# Granny_Safe_all_Inclusive.net
KiCad netlist of a schematic drawn in EAGLE
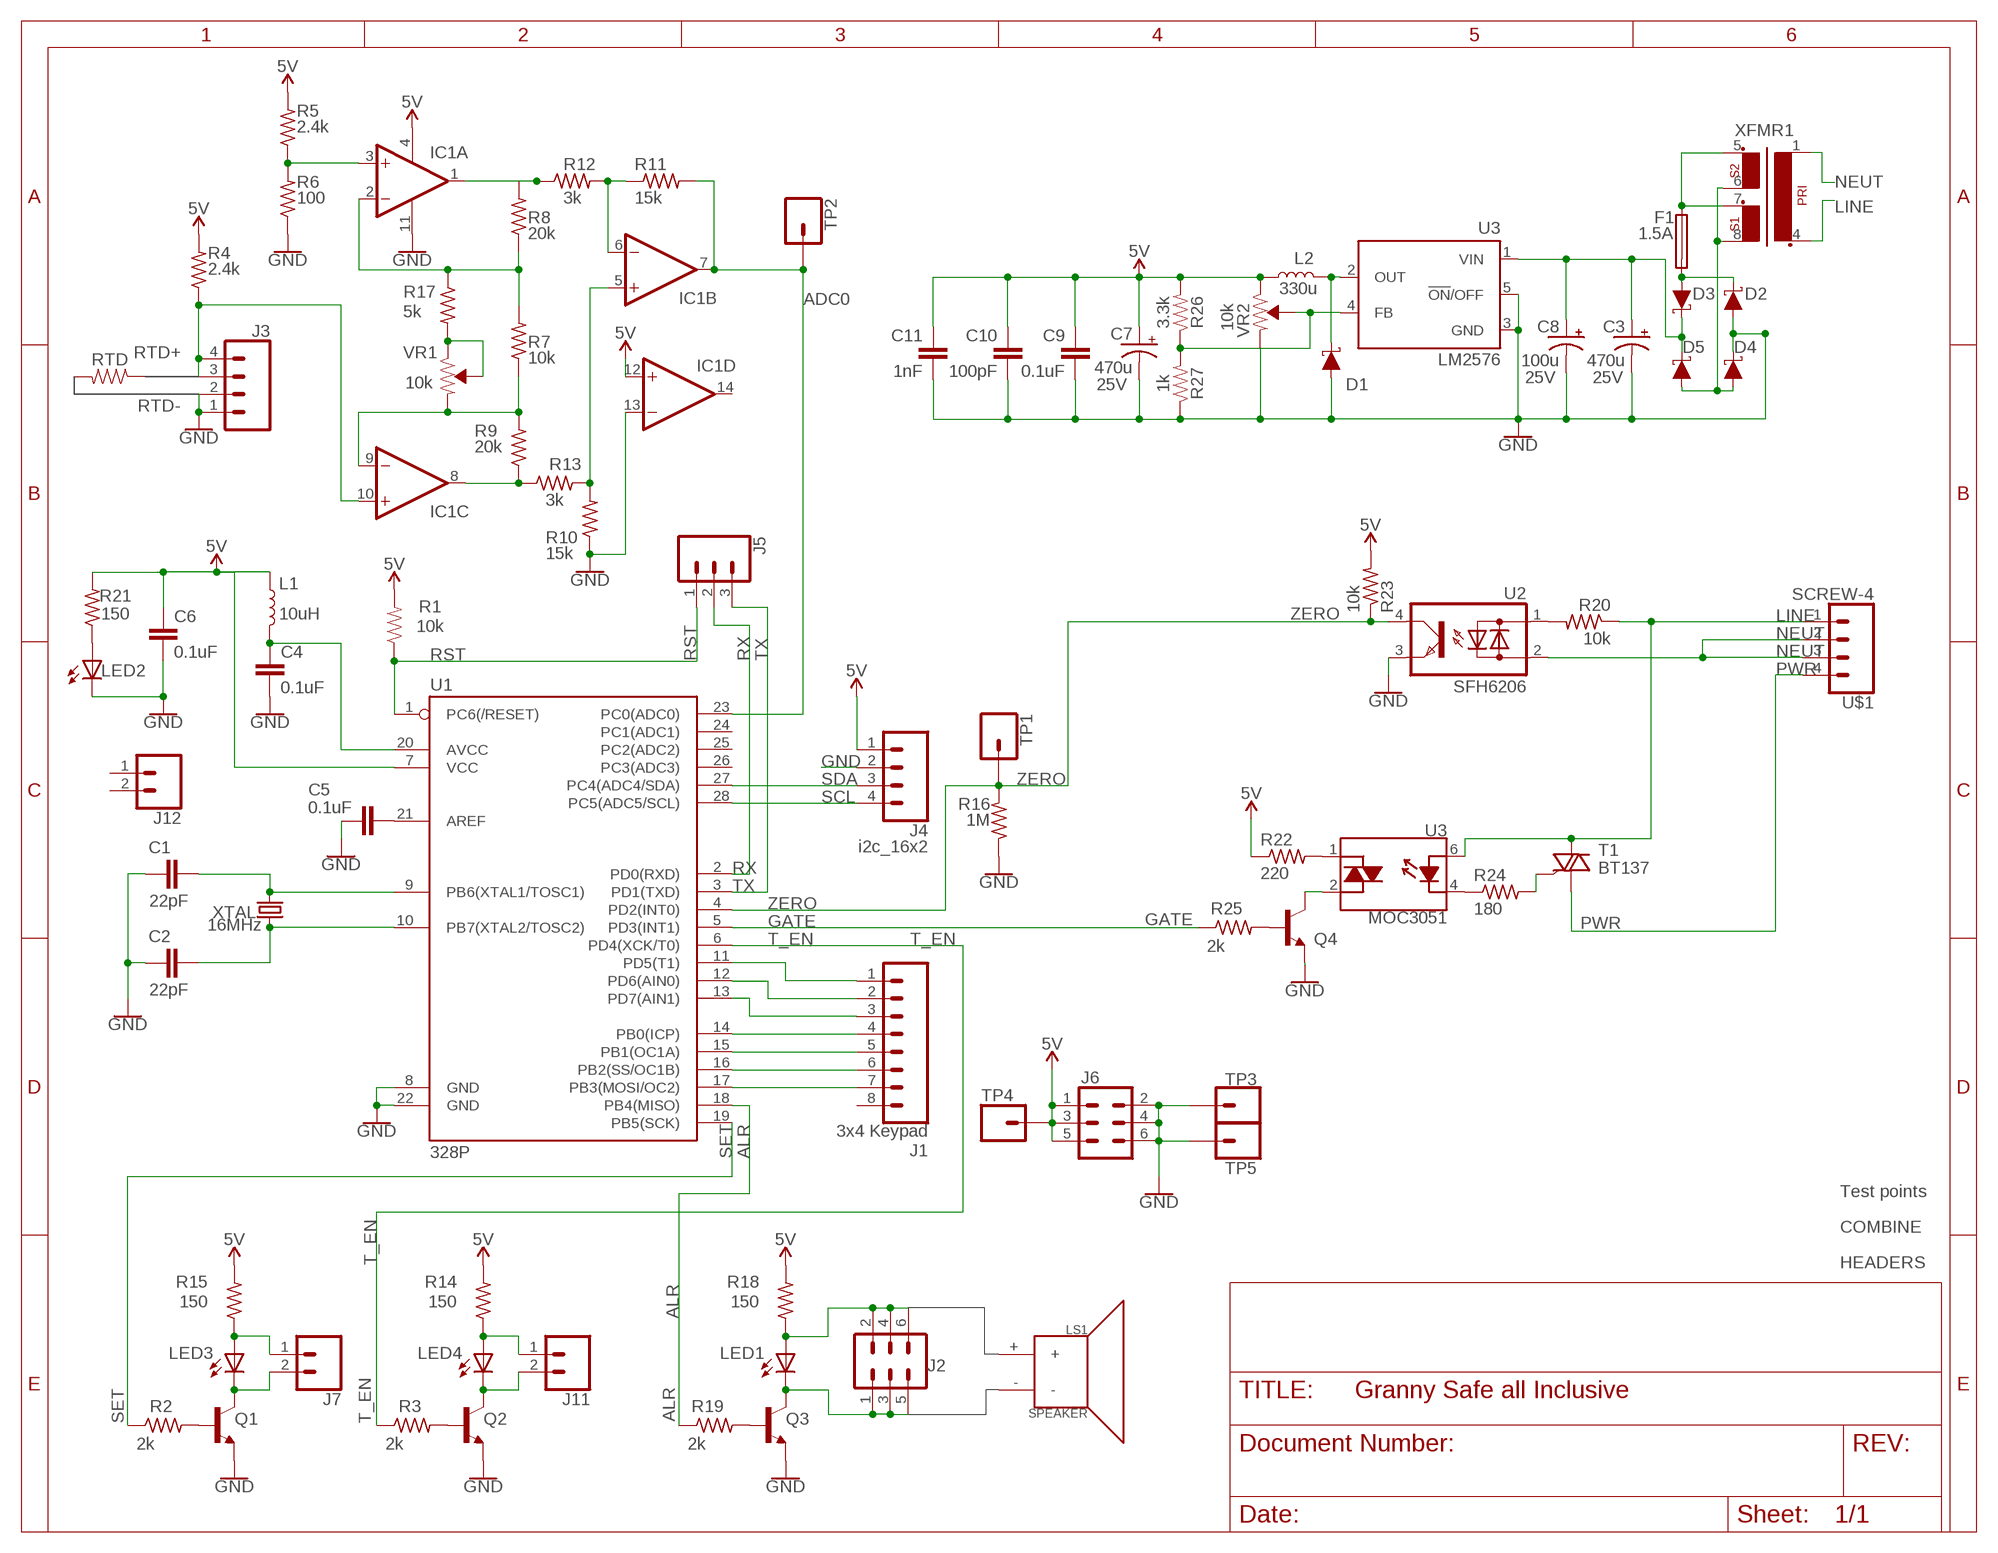
[diagram p0: schematic, sheet 1]

(export (version "E")
  (design (tool "Eeschema 10.0.6"))
  (components
    (comp (ref "C1")
      (value "22pF")
      (footprint "eagle-import:0603")
      (libsource (lib "eagle-import") (part "22PF-0603-50V-5%"))
    )
    (comp (ref "C2")
      (value "22pF")
      (footprint "eagle-import:0603")
      (libsource (lib "eagle-import") (part "22PF-0603-50V-5%"))
    )
    (comp (ref "C3")
      (value "470u")
      (footprint "eagle-import:E3,5-8")
      (libsource (lib "eagle-import") (part "CPOL-USE3.5-8"))
    )
    (comp (ref "C4")
      (value "0.1uF")
      (footprint "eagle-import:0603")
      (libsource (lib "eagle-import") (part "0.1UF-0603-25V-(+80/-20%)"))
    )
    (comp (ref "C5")
      (value "0.1uF")
      (footprint "eagle-import:0603")
      (libsource (lib "eagle-import") (part "0.1UF-0603-25V-(+80/-20%)"))
    )
    (comp (ref "C6")
      (value "0.1uF")
      (footprint "eagle-import:0603")
      (libsource (lib "eagle-import") (part "0.1UF-0603-25V-(+80/-20%)"))
    )
    (comp (ref "C7")
      (value "470u")
      (footprint "eagle-import:E3,5-8")
      (libsource (lib "eagle-import") (part "CPOL-USE3.5-8"))
    )
    (comp (ref "C8")
      (value "100u")
      (footprint "eagle-import:E2-5")
      (libsource (lib "eagle-import") (part "CPOL-USE2-5"))
    )
    (comp (ref "C9")
      (value "0.1uF")
      (footprint "eagle-import:0603")
      (libsource (lib "eagle-import") (part "0.1UF-0603-25V-5%"))
    )
    (comp (ref "C10")
      (value "100pF")
      (footprint "eagle-import:0603")
      (libsource (lib "eagle-import") (part "100PF-0603-50V-5%"))
    )
    (comp (ref "C11")
      (value "1nF")
      (footprint "eagle-import:0603")
      (libsource (lib "eagle-import") (part "1.0NF/1000PF-0603-50V-10%"))
    )
    (comp (ref "D1")
      (value "DIODE-SCHOTTKY-B340A")
      (footprint "eagle-import:SMA-DIODE")
      (libsource (lib "eagle-import") (part "DIODE-SCHOTTKY-B340A"))
    )
    (comp (ref "D2")
      (value "DIODE-SCHOTTKY-B340A")
      (footprint "eagle-import:SMA-DIODE")
      (libsource (lib "eagle-import") (part "DIODE-SCHOTTKY-B340A"))
    )
    (comp (ref "D3")
      (value "DIODE-SCHOTTKY-B340A")
      (footprint "eagle-import:SMA-DIODE")
      (libsource (lib "eagle-import") (part "DIODE-SCHOTTKY-B340A"))
    )
    (comp (ref "D4")
      (value "DIODE-SCHOTTKY-B340A")
      (footprint "eagle-import:SMA-DIODE")
      (libsource (lib "eagle-import") (part "DIODE-SCHOTTKY-B340A"))
    )
    (comp (ref "D5")
      (value "DIODE-SCHOTTKY-B340A")
      (footprint "eagle-import:SMA-DIODE")
      (libsource (lib "eagle-import") (part "DIODE-SCHOTTKY-B340A"))
    )
    (comp (ref "F1")
      (value "1.5A")
      (footprint "eagle-import:TE5")
      (libsource (lib "eagle-import") (part "TE5"))
    )
    (comp (ref "IC1")
      (value "MCP604SL")
      (footprint "eagle-import:SO14")
      (libsource (lib "eagle-import") (part "MCP604SL"))
    )
    (comp (ref "IC2")
      (value "LM2596S")
      (footprint "eagle-import:TO263-5")
      (fields (field (name "MF") "NATIONAL SEMICONDUCTOR") (field (name "MPN") "LM2596S-ADJ/NOPB"))
      (libsource (lib "eagle-import") (part "LM2596S"))
    )
    (comp (ref "J1")
      (value "3x4 Keypad")
      (footprint "eagle-import:1X08")
      (libsource (lib "eagle-import") (part "CONN_08{dblquote}"))
    )
    (comp (ref "J2")
      (value "FEMALE 2x3")
      (footprint "eagle-import:2X3")
      (libsource (lib "eagle-import") (part "CONN_03X2FEMALE"))
    )
    (comp (ref "J3")
      (value "SCREW-4")
      (footprint "eagle-import:SCREWTERMINAL-5MM-2")
      (libsource (lib "eagle-import") (part "SCREW-4"))
    )
    (comp (ref "J4")
      (value "i2c_16x2")
      (footprint "eagle-import:1X04")
      (libsource (lib "eagle-import") (part "CONN_04"))
    )
    (comp (ref "J5")
      (value "CONN_03")
      (footprint "eagle-import:1X03")
      (libsource (lib "eagle-import") (part "CONN_03"))
    )
    (comp (ref "J6")
      (value "FEMALE 2x3")
      (footprint "eagle-import:2X3")
      (libsource (lib "eagle-import") (part "CONN_03X2FEMALE"))
    )
    (comp (ref "J7")
      (value "CONN_02")
      (footprint "eagle-import:1X02")
      (libsource (lib "eagle-import") (part "CONN_02"))
    )
    (comp (ref "J11")
      (value "CONN_02")
      (footprint "eagle-import:1X02")
      (libsource (lib "eagle-import") (part "CONN_02"))
    )
    (comp (ref "J12")
      (value "CONN_02")
      (footprint "eagle-import:1X02")
      (libsource (lib "eagle-import") (part "CONN_02"))
    )
    (comp (ref "L1")
      (value "10uH")
      (footprint "eagle-import:0603")
      (libsource (lib "eagle-import") (part "INDUCTOR-0603-33NH"))
    )
    (comp (ref "L2")
      (value "INDUCTOR")
      (footprint "eagle-import:CR75")
      (libsource (lib "eagle-import") (part "INDUCTOR"))
    )
    (comp (ref "LED1")
      (value "LED5MM")
      (footprint "eagle-import:LED5MM")
      (libsource (lib "eagle-import") (part "LED5MM"))
    )
    (comp (ref "LED2")
      (value "LED5MM")
      (footprint "eagle-import:LED5MM")
      (libsource (lib "eagle-import") (part "LED5MM"))
    )
    (comp (ref "LED3")
      (value "LED5MM")
      (footprint "eagle-import:LED5MM")
      (libsource (lib "eagle-import") (part "LED5MM"))
    )
    (comp (ref "LED4")
      (value "LED5MM")
      (footprint "eagle-import:LED5MM")
      (libsource (lib "eagle-import") (part "LED5MM"))
    )
    (comp (ref "LS1")
      (value "SPEAKER")
      (footprint "eagle-import:PCB_MOUNT_SPEAKER")
      (libsource (lib "eagle-import") (part "SPEAKER"))
    )
    (comp (ref "Q1")
      (value "TRANS_NPN-MMBTA42")
      (footprint "eagle-import:SOT23-3")
      (libsource (lib "eagle-import") (part "TRANS_NPN-MMBTA42"))
    )
    (comp (ref "Q2")
      (value "TRANS_NPN-MMBTA42")
      (footprint "eagle-import:SOT23-3")
      (libsource (lib "eagle-import") (part "TRANS_NPN-MMBTA42"))
    )
    (comp (ref "Q3")
      (value "TRANS_NPN-MMBTA42")
      (footprint "eagle-import:SOT23-3")
      (libsource (lib "eagle-import") (part "TRANS_NPN-MMBTA42"))
    )
    (comp (ref "Q4")
      (value "2N3904")
      (footprint "eagle-import:SOT23-3")
      (libsource (lib "eagle-import") (part "TRANS_NPN-MMBTA42"))
    )
    (comp (ref "R1")
      (value "10k")
      (footprint "eagle-import:0603")
      (libsource (lib "eagle-import") (part "10KOHM-0603-1/10W-1%"))
    )
    (comp (ref "R2")
      (value "2k")
      (footprint "eagle-import:R0603")
      (libsource (lib "eagle-import") (part "R-US_R0603"))
    )
    (comp (ref "R3")
      (value "2k")
      (footprint "eagle-import:R0603")
      (libsource (lib "eagle-import") (part "R-US_R0603"))
    )
    (comp (ref "R4")
      (value "2.4k")
      (footprint "eagle-import:R0603")
      (libsource (lib "eagle-import") (part "resistor_348_R-US_R0603"))
    )
    (comp (ref "R5")
      (value "2.4k")
      (footprint "eagle-import:R0603")
      (libsource (lib "eagle-import") (part "resistor_348_R-US_R0603"))
    )
    (comp (ref "R6")
      (value "100")
      (footprint "eagle-import:R0603")
      (libsource (lib "eagle-import") (part "resistor_348_R-US_R0603"))
    )
    (comp (ref "R7")
      (value "10k")
      (footprint "eagle-import:R0603")
      (libsource (lib "eagle-import") (part "resistor_348_R-US_R0603"))
    )
    (comp (ref "R8")
      (value "20k")
      (footprint "eagle-import:R0603")
      (libsource (lib "eagle-import") (part "resistor_348_R-US_R0603"))
    )
    (comp (ref "R9")
      (value "20k")
      (footprint "eagle-import:R0603")
      (libsource (lib "eagle-import") (part "resistor_348_R-US_R0603"))
    )
    (comp (ref "R10")
      (value "15k")
      (footprint "eagle-import:R0603")
      (libsource (lib "eagle-import") (part "resistor_348_R-US_R0603"))
    )
    (comp (ref "R11")
      (value "15k")
      (footprint "eagle-import:R0603")
      (libsource (lib "eagle-import") (part "resistor_348_R-US_R0603"))
    )
    (comp (ref "R12")
      (value "3k")
      (footprint "eagle-import:R0603")
      (libsource (lib "eagle-import") (part "resistor_348_R-US_R0603"))
    )
    (comp (ref "R13")
      (value "3k")
      (footprint "eagle-import:R0603")
      (libsource (lib "eagle-import") (part "resistor_348_R-US_R0603"))
    )
    (comp (ref "R14")
      (value "150")
      (footprint "eagle-import:R0603")
      (libsource (lib "eagle-import") (part "R-US_R0603"))
    )
    (comp (ref "R15")
      (value "150")
      (footprint "eagle-import:R0603")
      (libsource (lib "eagle-import") (part "R-US_R0603"))
    )
    (comp (ref "R16")
      (value "1M")
      (footprint "eagle-import:R0603")
      (libsource (lib "eagle-import") (part "resistor_348_R-US_R0603"))
    )
    (comp (ref "R17")
      (value "5k")
      (footprint "eagle-import:R0603")
      (libsource (lib "eagle-import") (part "resistor_348_R-US_R0603"))
    )
    (comp (ref "R18")
      (value "150")
      (footprint "eagle-import:R0603")
      (libsource (lib "eagle-import") (part "R-US_R0603"))
    )
    (comp (ref "R19")
      (value "2k")
      (footprint "eagle-import:R0603")
      (libsource (lib "eagle-import") (part "R-US_R0603"))
    )
    (comp (ref "R20")
      (value "10k")
      (footprint "eagle-import:R0603")
      (libsource (lib "eagle-import") (part "R-US_R0603"))
    )
    (comp (ref "R21")
      (value "150")
      (footprint "eagle-import:R0603")
      (libsource (lib "eagle-import") (part "R-US_R0603"))
    )
    (comp (ref "R22")
      (value "220")
      (footprint "eagle-import:R0603")
      (libsource (lib "eagle-import") (part "R-US_R0603"))
    )
    (comp (ref "R23")
      (value "10k")
      (footprint "eagle-import:R0603")
      (libsource (lib "eagle-import") (part "R-US_R0603"))
    )
    (comp (ref "R24")
      (value "180")
      (footprint "eagle-import:R0603")
      (libsource (lib "eagle-import") (part "R-US_R0603"))
    )
    (comp (ref "R25")
      (value "2k")
      (footprint "eagle-import:R0603")
      (libsource (lib "eagle-import") (part "R-US_R0603"))
    )
    (comp (ref "R26")
      (value "3.3k")
      (footprint "eagle-import:0603")
      (libsource (lib "eagle-import") (part "3.3KOHM-0603-1/10W-1%"))
    )
    (comp (ref "R27")
      (value "1k")
      (footprint "eagle-import:0603")
      (libsource (lib "eagle-import") (part "1KOHM-0603-1/10W-1%"))
    )
    (comp (ref "RTD")
      (value "10KOHM-HORIZ-1/4W-1%")
      (footprint "eagle-import:AXIAL-0.3")
      (libsource (lib "eagle-import") (part "10KOHM-HORIZ-1/4W-1%"))
    )
    (comp (ref "T1")
      (value "BT137")
      (footprint "eagle-import:TO220BV")
      (libsource (lib "eagle-import") (part "BT137"))
    )
    (comp (ref "TP1")
      (value "CONN_01")
      (footprint "eagle-import:1X01")
      (libsource (lib "eagle-import") (part "CONN_01"))
    )
    (comp (ref "TP2")
      (value "CONN_01")
      (footprint "eagle-import:1X01")
      (libsource (lib "eagle-import") (part "CONN_01"))
    )
    (comp (ref "TP3")
      (value "CONN_01")
      (footprint "eagle-import:1X01")
      (libsource (lib "eagle-import") (part "CONN_01"))
    )
    (comp (ref "TP4")
      (value "CONN_01")
      (footprint "eagle-import:1X01")
      (libsource (lib "eagle-import") (part "CONN_01"))
    )
    (comp (ref "TP5")
      (value "CONN_01")
      (footprint "eagle-import:1X01")
      (libsource (lib "eagle-import") (part "CONN_01"))
    )
    (comp (ref "U$1")
      (value "SCREW-4")
      (footprint "eagle-import:SCREWTERMINAL-5MM-2")
      (libsource (lib "eagle-import") (part "SCREW-4"))
    )
    (comp (ref "U1")
      (value "328P")
      (footprint "eagle-import:DIP28")
      (libsource (lib "eagle-import") (part "ATMEGA328P_PDIP"))
    )
    (comp (ref "U2")
      (value "SFH6206")
      (footprint "eagle-import:DIL4-SMD")
      (fields (field (name "MF") "VISHAY/TELEFUNKEN") (field (name "MPN") "SFH6206-3"))
      (libsource (lib "eagle-import") (part "SFH6206"))
    )
    (comp (ref "U3")
      (value "MOC3051")
      (footprint "eagle-import:DIP8SMD")
      (libsource (lib "eagle-import") (part "MOC3051"))
    )
    (comp (ref "VR1")
      (value "10k")
      (footprint "eagle-import:TRIMPOT-SMD-3MM-CLOSED")
      (libsource (lib "eagle-import") (part "TRIMPOT-SMD-3MM-CLOSED-1/8W-20%"))
    )
    (comp (ref "VR2")
      (value "10k")
      (footprint "eagle-import:TRIMPOT-SMD-TC33X")
      (libsource (lib "eagle-import") (part "TRIMPOT-SMD-3MM-OPEN-1/10W-25%"))
    )
    (comp (ref "XFMR1")
      (value "EE20-2")
      (footprint "eagle-import:EE20-2")
      (libsource (lib "eagle-import") (part "EE20-2"))
    )
    (comp (ref "XTAL")
      (value "16MHz")
      (footprint "eagle-import:HC49US")
      (libsource (lib "eagle-import") (part "CRYSTAL-16MHZPTH-HC49US"))
    )
  )
  (nets
    (net (code "1") (name "/ADC0") (class "Default")
      (node (ref "IC1") (pin "7") (pinfunction "OUT_7") (pintype "output"))
      (node (ref "R11") (pin "2") (pinfunction "2_2") (pintype "passive"))
      (node (ref "TP2") (pin "1") (pinfunction "1_1") (pintype "passive"))
      (node (ref "U1") (pin "23") (pinfunction "PC0(ADC0)_23") (pintype "bidirectional"))
    )
    (net (code "2") (name "/ALR") (class "Default")
      (node (ref "R19") (pin "1") (pinfunction "1_1") (pintype "passive"))
      (node (ref "U1") (pin "18") (pinfunction "PB4(MISO)_18") (pintype "bidirectional"))
    )
    (net (code "3") (name "/GATE") (class "Default")
      (node (ref "R25") (pin "1") (pinfunction "1_1") (pintype "passive"))
      (node (ref "U1") (pin "5") (pinfunction "PD3(INT1)_5") (pintype "bidirectional"))
    )
    (net (code "4") (name "/LINE") (class "Default")
      (node (ref "R20") (pin "1") (pinfunction "1_1") (pintype "passive"))
      (node (ref "T1") (pin "T2") (pinfunction "A2_T2") (pintype "passive"))
      (node (ref "U$1") (pin "1") (pinfunction "1_1") (pintype "passive"))
      (node (ref "U3") (pin "6") (pinfunction "6_6") (pintype "bidirectional"))
      (node (ref "XFMR1") (pin "4") (pinfunction "2_4") (pintype "passive"))
    )
    (net (code "5") (name "/NEUT") (class "Default")
      (node (ref "U$1") (pin "2") (pinfunction "2_2") (pintype "passive"))
      (node (ref "U$1") (pin "3") (pinfunction "3_3") (pintype "passive"))
      (node (ref "U2") (pin "2") (pinfunction "AC2_2") (pintype "passive"))
      (node (ref "XFMR1") (pin "1") (pinfunction "1_1") (pintype "passive"))
    )
    (net (code "6") (name "/PWR") (class "Default")
      (node (ref "T1") (pin "T1") (pinfunction "A1_T1") (pintype "passive"))
      (node (ref "U$1") (pin "4") (pinfunction "4_4") (pintype "passive"))
    )
    (net (code "7") (name "/RST") (class "Default")
      (node (ref "J5") (pin "1") (pinfunction "1_1") (pintype "passive"))
      (node (ref "R1") (pin "1") (pinfunction "1_1") (pintype "passive"))
      (node (ref "U1") (pin "1") (pinfunction "PC6(/RESET)_1") (pintype "bidirectional"))
    )
    (net (code "8") (name "/RX") (class "Default")
      (node (ref "J5") (pin "2") (pinfunction "2_2") (pintype "passive"))
      (node (ref "U1") (pin "2") (pinfunction "PD0(RXD)_2") (pintype "bidirectional"))
    )
    (net (code "9") (name "/SCL") (class "Default")
      (node (ref "J4") (pin "4") (pinfunction "4_4") (pintype "passive"))
      (node (ref "U1") (pin "28") (pinfunction "PC5(ADC5/SCL)_28") (pintype "bidirectional"))
    )
    (net (code "10") (name "/SDA") (class "Default")
      (node (ref "J4") (pin "3") (pinfunction "3_3") (pintype "passive"))
      (node (ref "U1") (pin "27") (pinfunction "PC4(ADC4/SDA)_27") (pintype "bidirectional"))
    )
    (net (code "11") (name "/SET") (class "Default")
      (node (ref "R2") (pin "1") (pinfunction "1_1") (pintype "passive"))
      (node (ref "U1") (pin "19") (pinfunction "PB5(SCK)_19") (pintype "bidirectional"))
    )
    (net (code "12") (name "/TX") (class "Default")
      (node (ref "J5") (pin "3") (pinfunction "3_3") (pintype "passive"))
      (node (ref "U1") (pin "3") (pinfunction "PD1(TXD)_3") (pintype "bidirectional"))
    )
    (net (code "13") (name "/T_EN") (class "Default")
      (node (ref "R3") (pin "1") (pinfunction "1_1") (pintype "passive"))
      (node (ref "U1") (pin "6") (pinfunction "PD4(XCK/T0)_6") (pintype "bidirectional"))
    )
    (net (code "14") (name "/ZERO") (class "Default")
      (node (ref "R16") (pin "2") (pinfunction "2_2") (pintype "passive"))
      (node (ref "R23") (pin "1") (pinfunction "1_1") (pintype "passive"))
      (node (ref "TP1") (pin "1") (pinfunction "1_1") (pintype "passive"))
      (node (ref "U1") (pin "4") (pinfunction "PD2(INT0)_4") (pintype "bidirectional"))
      (node (ref "U2") (pin "4") (pinfunction "C_4") (pintype "passive"))
    )
    (net (code "15") (name "5V") (class "Default")
      (node (ref "C10") (pin "1") (pinfunction "1_1") (pintype "passive"))
      (node (ref "C11") (pin "1") (pinfunction "1_1") (pintype "passive"))
      (node (ref "C6") (pin "1") (pinfunction "1_1") (pintype "passive"))
      (node (ref "C7") (pin "+") (pinfunction "+_+") (pintype "passive"))
      (node (ref "C9") (pin "1") (pinfunction "1_1") (pintype "passive"))
      (node (ref "IC1") (pin "12") (pinfunction "+IN_12") (pintype "input"))
      (node (ref "IC1") (pin "4") (pinfunction "V+_4") (pintype "power_in"))
      (node (ref "J4") (pin "1") (pinfunction "1_1") (pintype "passive"))
      (node (ref "J6") (pin "1") (pinfunction "1_1") (pintype "bidirectional"))
      (node (ref "J6") (pin "3") (pinfunction "3_3") (pintype "bidirectional"))
      (node (ref "J6") (pin "5") (pinfunction "5_5") (pintype "bidirectional"))
      (node (ref "L1") (pin "1") (pinfunction "1_1") (pintype "passive"))
      (node (ref "L2") (pin "P$2") (pinfunction "2_P$2") (pintype "passive"))
      (node (ref "R1") (pin "2") (pinfunction "2_2") (pintype "passive"))
      (node (ref "R14") (pin "2") (pinfunction "2_2") (pintype "passive"))
      (node (ref "R15") (pin "2") (pinfunction "2_2") (pintype "passive"))
      (node (ref "R18") (pin "2") (pinfunction "2_2") (pintype "passive"))
      (node (ref "R21") (pin "2") (pinfunction "2_2") (pintype "passive"))
      (node (ref "R22") (pin "1") (pinfunction "1_1") (pintype "passive"))
      (node (ref "R23") (pin "2") (pinfunction "2_2") (pintype "passive"))
      (node (ref "R26") (pin "2") (pinfunction "2_2") (pintype "passive"))
      (node (ref "R4") (pin "2") (pinfunction "2_2") (pintype "passive"))
      (node (ref "R5") (pin "2") (pinfunction "2_2") (pintype "passive"))
      (node (ref "TP4") (pin "1") (pinfunction "1_1") (pintype "passive"))
      (node (ref "U1") (pin "7") (pinfunction "VCC_7") (pintype "bidirectional"))
      (node (ref "VR2") (pin "1") (pinfunction "CW_1") (pintype "passive"))
    )
    (net (code "16") (name "GND") (class "Default")
      (node (ref "C1") (pin "1") (pinfunction "1_1") (pintype "passive"))
      (node (ref "C10") (pin "2") (pinfunction "2_2") (pintype "passive"))
      (node (ref "C11") (pin "2") (pinfunction "2_2") (pintype "passive"))
      (node (ref "C2") (pin "1") (pinfunction "1_1") (pintype "passive"))
      (node (ref "C3") (pin "-") (pinfunction "-_-") (pintype "passive"))
      (node (ref "C4") (pin "2") (pinfunction "2_2") (pintype "passive"))
      (node (ref "C5") (pin "2") (pinfunction "2_2") (pintype "passive"))
      (node (ref "C6") (pin "2") (pinfunction "2_2") (pintype "passive"))
      (node (ref "C7") (pin "-") (pinfunction "-_-") (pintype "passive"))
      (node (ref "C8") (pin "-") (pinfunction "-_-") (pintype "passive"))
      (node (ref "C9") (pin "2") (pinfunction "2_2") (pintype "passive"))
      (node (ref "D1") (pin "A") (pinfunction "A_A") (pintype "passive"))
      (node (ref "D2") (pin "A") (pinfunction "A_A") (pintype "passive"))
      (node (ref "D4") (pin "C") (pinfunction "C_C") (pintype "passive"))
      (node (ref "IC1") (pin "11") (pinfunction "V-_11") (pintype "power_in"))
      (node (ref "IC1") (pin "13") (pinfunction "-IN_13") (pintype "input"))
      (node (ref "IC2") (pin "3") (pinfunction "GND_3") (pintype "power_in"))
      (node (ref "IC2") (pin "5") (pinfunction "~{ON}/OFF_5") (pintype "input"))
      (node (ref "J3") (pin "1") (pinfunction "1_1") (pintype "passive"))
      (node (ref "J3") (pin "2") (pinfunction "2_2") (pintype "passive"))
      (node (ref "J4") (pin "2") (pinfunction "2_2") (pintype "passive"))
      (node (ref "J6") (pin "2") (pinfunction "2_2") (pintype "bidirectional"))
      (node (ref "J6") (pin "4") (pinfunction "4_4") (pintype "bidirectional"))
      (node (ref "J6") (pin "6") (pinfunction "6_6") (pintype "bidirectional"))
      (node (ref "LED2") (pin "K") (pinfunction "C_K") (pintype "passive"))
      (node (ref "Q1") (pin "2") (pinfunction "E_2") (pintype "passive"))
      (node (ref "Q2") (pin "2") (pinfunction "E_2") (pintype "passive"))
      (node (ref "Q3") (pin "2") (pinfunction "E_2") (pintype "passive"))
      (node (ref "Q4") (pin "2") (pinfunction "E_2") (pintype "passive"))
      (node (ref "R10") (pin "1") (pinfunction "1_1") (pintype "passive"))
      (node (ref "R16") (pin "1") (pinfunction "1_1") (pintype "passive"))
      (node (ref "R27") (pin "1") (pinfunction "1_1") (pintype "passive"))
      (node (ref "R6") (pin "1") (pinfunction "1_1") (pintype "passive"))
      (node (ref "TP3") (pin "1") (pinfunction "1_1") (pintype "passive"))
      (node (ref "TP5") (pin "1") (pinfunction "1_1") (pintype "passive"))
      (node (ref "U1") (pin "22") (pinfunction "GND_22") (pintype "bidirectional"))
      (node (ref "U1") (pin "8") (pinfunction "GND_8") (pintype "bidirectional"))
      (node (ref "U2") (pin "3") (pinfunction "E_3") (pintype "passive"))
      (node (ref "VR2") (pin "3") (pinfunction "CCW_3") (pintype "passive"))
    )
    (net (code "17") (name "Net-(D2-PadC)") (class "Default")
      (node (ref "D2") (pin "C") (pinfunction "C_C") (pintype "passive"))
      (node (ref "D3") (pin "A") (pinfunction "A_A") (pintype "passive"))
      (node (ref "F1") (pin "2") (pinfunction "2_2") (pintype "passive"))
    )
    (net (code "18") (name "Net-(IC1A-+IN)") (class "Default")
      (node (ref "IC1") (pin "3") (pinfunction "+IN_3") (pintype "input"))
      (node (ref "R5") (pin "1") (pinfunction "1_1") (pintype "passive"))
      (node (ref "R6") (pin "2") (pinfunction "2_2") (pintype "passive"))
    )
    (net (code "19") (name "Net-(IC1A--IN)") (class "Default")
      (node (ref "IC1") (pin "2") (pinfunction "-IN_2") (pintype "input"))
      (node (ref "R17") (pin "1") (pinfunction "1_1") (pintype "passive"))
      (node (ref "R7") (pin "2") (pinfunction "2_2") (pintype "passive"))
      (node (ref "R8") (pin "1") (pinfunction "1_1") (pintype "passive"))
    )
    (net (code "20") (name "Net-(IC1A-OUT)") (class "Default")
      (node (ref "IC1") (pin "1") (pinfunction "OUT_1") (pintype "output"))
      (node (ref "R12") (pin "1") (pinfunction "1_1") (pintype "passive"))
      (node (ref "R8") (pin "2") (pinfunction "2_2") (pintype "passive"))
    )
    (net (code "21") (name "Net-(IC1B-+IN)") (class "Default")
      (node (ref "IC1") (pin "5") (pinfunction "+IN_5") (pintype "input"))
      (node (ref "R10") (pin "2") (pinfunction "2_2") (pintype "passive"))
      (node (ref "R13") (pin "2") (pinfunction "2_2") (pintype "passive"))
    )
    (net (code "22") (name "Net-(IC1B--IN)") (class "Default")
      (node (ref "IC1") (pin "6") (pinfunction "-IN_6") (pintype "input"))
      (node (ref "R11") (pin "1") (pinfunction "1_1") (pintype "passive"))
      (node (ref "R12") (pin "2") (pinfunction "2_2") (pintype "passive"))
    )
    (net (code "23") (name "Net-(IC1C-+IN)") (class "Default")
      (node (ref "IC1") (pin "10") (pinfunction "+IN_10") (pintype "input"))
      (node (ref "J3") (pin "3") (pinfunction "3_3") (pintype "passive"))
      (node (ref "J3") (pin "4") (pinfunction "4_4") (pintype "passive"))
      (node (ref "R4") (pin "1") (pinfunction "1_1") (pintype "passive"))
    )
    (net (code "24") (name "Net-(IC1C--IN)") (class "Default")
      (node (ref "IC1") (pin "9") (pinfunction "-IN_9") (pintype "input"))
      (node (ref "R7") (pin "1") (pinfunction "1_1") (pintype "passive"))
      (node (ref "R9") (pin "2") (pinfunction "2_2") (pintype "passive"))
      (node (ref "VR1") (pin "1") (pinfunction "CCW_1") (pintype "passive"))
    )
    (net (code "25") (name "Net-(IC1C-OUT)") (class "Default")
      (node (ref "IC1") (pin "8") (pinfunction "OUT_8") (pintype "output"))
      (node (ref "R13") (pin "1") (pinfunction "1_1") (pintype "passive"))
      (node (ref "R9") (pin "1") (pinfunction "1_1") (pintype "passive"))
    )
    (net (code "26") (name "Net-(IC2-FB)") (class "Default")
      (node (ref "IC2") (pin "4") (pinfunction "FB_4") (pintype "input"))
      (node (ref "R26") (pin "1") (pinfunction "1_1") (pintype "passive"))
      (node (ref "R27") (pin "2") (pinfunction "2_2") (pintype "passive"))
      (node (ref "VR2") (pin "2") (pinfunction "WIPER_2") (pintype "passive"))
    )
    (net (code "27") (name "Net-(IC2-OUT)") (class "Default")
      (node (ref "D1") (pin "C") (pinfunction "C_C") (pintype "passive"))
      (node (ref "IC2") (pin "2") (pinfunction "OUT_2") (pintype "output"))
      (node (ref "L2") (pin "P$1") (pinfunction "1_P$1") (pintype "passive"))
    )
    (net (code "28") (name "Net-(IC2-VIN)") (class "Default")
      (node (ref "C3") (pin "+") (pinfunction "+_+") (pintype "passive"))
      (node (ref "C8") (pin "+") (pinfunction "+_+") (pintype "passive"))
      (node (ref "D3") (pin "C") (pinfunction "C_C") (pintype "passive"))
      (node (ref "D5") (pin "C") (pinfunction "C_C") (pintype "passive"))
      (node (ref "IC2") (pin "1") (pinfunction "VIN_1") (pintype "input"))
    )
    (net (code "29") (name "Net-(J2-Pad2)") (class "Default")
      (node (ref "J2") (pin "2") (pinfunction "2_2") (pintype "bidirectional"))
      (node (ref "J2") (pin "4") (pinfunction "4_4") (pintype "bidirectional"))
      (node (ref "J2") (pin "6") (pinfunction "6_6") (pintype "bidirectional"))
      (node (ref "LED1") (pin "A") (pinfunction "A_A") (pintype "passive"))
      (node (ref "R18") (pin "1") (pinfunction "1_1") (pintype "passive"))
    )
    (net (code "30") (name "Net-(J7-Pad1)") (class "Default")
      (node (ref "J7") (pin "1") (pinfunction "1_1") (pintype "passive"))
      (node (ref "LED3") (pin "A") (pinfunction "A_A") (pintype "passive"))
      (node (ref "R15") (pin "1") (pinfunction "1_1") (pintype "passive"))
    )
    (net (code "31") (name "Net-(J11-Pad1)") (class "Default")
      (node (ref "J11") (pin "1") (pinfunction "1_1") (pintype "passive"))
      (node (ref "LED4") (pin "A") (pinfunction "A_A") (pintype "passive"))
      (node (ref "R14") (pin "1") (pinfunction "1_1") (pintype "passive"))
    )
    (net (code "32") (name "Net-(LED1-C)") (class "Default")
      (node (ref "J2") (pin "1") (pinfunction "1_1") (pintype "bidirectional"))
      (node (ref "J2") (pin "3") (pinfunction "3_3") (pintype "bidirectional"))
      (node (ref "J2") (pin "5") (pinfunction "5_5") (pintype "bidirectional"))
      (node (ref "LED1") (pin "K") (pinfunction "C_K") (pintype "passive"))
      (node (ref "Q3") (pin "3") (pinfunction "C_3") (pintype "passive"))
    )
    (net (code "33") (name "Net-(LED2-PadA)") (class "Default")
      (node (ref "LED2") (pin "A") (pinfunction "A_A") (pintype "passive"))
      (node (ref "R21") (pin "1") (pinfunction "1_1") (pintype "passive"))
    )
    (net (code "34") (name "Net-(LED3-C)") (class "Default")
      (node (ref "J7") (pin "2") (pinfunction "2_2") (pintype "passive"))
      (node (ref "LED3") (pin "K") (pinfunction "C_K") (pintype "passive"))
      (node (ref "Q1") (pin "3") (pinfunction "C_3") (pintype "passive"))
    )
    (net (code "35") (name "Net-(LED4-C)") (class "Default")
      (node (ref "J11") (pin "2") (pinfunction "2_2") (pintype "passive"))
      (node (ref "LED4") (pin "K") (pinfunction "C_K") (pintype "passive"))
      (node (ref "Q2") (pin "3") (pinfunction "C_3") (pintype "passive"))
    )
    (net (code "36") (name "Net-(Q1-B)") (class "Default")
      (node (ref "Q1") (pin "1") (pinfunction "B_1") (pintype "passive"))
      (node (ref "R2") (pin "2") (pinfunction "2_2") (pintype "passive"))
    )
    (net (code "37") (name "Net-(Q2-B)") (class "Default")
      (node (ref "Q2") (pin "1") (pinfunction "B_1") (pintype "passive"))
      (node (ref "R3") (pin "2") (pinfunction "2_2") (pintype "passive"))
    )
    (net (code "38") (name "Net-(Q3-B)") (class "Default")
      (node (ref "Q3") (pin "1") (pinfunction "B_1") (pintype "passive"))
      (node (ref "R19") (pin "2") (pinfunction "2_2") (pintype "passive"))
    )
    (net (code "39") (name "Net-(Q4-B)") (class "Default")
      (node (ref "Q4") (pin "1") (pinfunction "B_1") (pintype "passive"))
      (node (ref "R25") (pin "2") (pinfunction "2_2") (pintype "passive"))
    )
    (net (code "40") (name "Net-(Q4-C)") (class "Default")
      (node (ref "Q4") (pin "3") (pinfunction "C_3") (pintype "passive"))
      (node (ref "U3") (pin "2") (pinfunction "2_2") (pintype "bidirectional"))
    )
    (net (code "41") (name "Net-(R22-Pad2)") (class "Default")
      (node (ref "R22") (pin "2") (pinfunction "2_2") (pintype "passive"))
      (node (ref "U3") (pin "1") (pinfunction "1_1") (pintype "bidirectional"))
    )
    (net (code "42") (name "Net-(R24-Pad1)") (class "Default")
      (node (ref "R24") (pin "1") (pinfunction "1_1") (pintype "passive"))
      (node (ref "U3") (pin "4") (pinfunction "4_4") (pintype "bidirectional"))
    )
    (net (code "43") (name "Net-(R24-Pad2)") (class "Default")
      (node (ref "R24") (pin "2") (pinfunction "2_2") (pintype "passive"))
      (node (ref "T1") (pin "G") (pinfunction "G_G") (pintype "passive"))
    )
    (net (code "44") (name "Net-(U1-AREF)") (class "Default")
      (node (ref "C5") (pin "1") (pinfunction "1_1") (pintype "passive"))
      (node (ref "U1") (pin "21") (pinfunction "AREF_21") (pintype "bidirectional"))
    )
    (net (code "45") (name "Net-(U1-AVCC)") (class "Default")
      (node (ref "C4") (pin "1") (pinfunction "1_1") (pintype "passive"))
      (node (ref "L1") (pin "2") (pinfunction "2_2") (pintype "passive"))
      (node (ref "U1") (pin "20") (pinfunction "AVCC_20") (pintype "bidirectional"))
    )
    (net (code "46") (name "Net-(U1-PB0(ICP))") (class "Default")
      (node (ref "J1") (pin "4") (pinfunction "4_4") (pintype "passive"))
      (node (ref "U1") (pin "14") (pinfunction "PB0(ICP)_14") (pintype "bidirectional"))
    )
    (net (code "47") (name "Net-(U1-PB1(OC1A))") (class "Default")
      (node (ref "J1") (pin "5") (pinfunction "5_5") (pintype "passive"))
      (node (ref "U1") (pin "15") (pinfunction "PB1(OC1A)_15") (pintype "bidirectional"))
    )
    (net (code "48") (name "Net-(U1-PB2(SS{slash}OC1B))") (class "Default")
      (node (ref "J1") (pin "6") (pinfunction "6_6") (pintype "passive"))
      (node (ref "U1") (pin "16") (pinfunction "PB2(SS/OC1B)_16") (pintype "bidirectional"))
    )
    (net (code "49") (name "Net-(U1-PB3(MOSI{slash}OC2))") (class "Default")
      (node (ref "J1") (pin "7") (pinfunction "7_7") (pintype "passive"))
      (node (ref "U1") (pin "17") (pinfunction "PB3(MOSI/OC2)_17") (pintype "bidirectional"))
    )
    (net (code "50") (name "Net-(U1-PB6(XTAL1{slash}TOSC1))") (class "Default")
      (node (ref "C1") (pin "2") (pinfunction "2_2") (pintype "passive"))
      (node (ref "U1") (pin "9") (pinfunction "PB6(XTAL1/TOSC1)_9") (pintype "bidirectional"))
      (node (ref "XTAL") (pin "2") (pinfunction "2_2") (pintype "passive"))
    )
    (net (code "51") (name "Net-(U1-PB7(XTAL2{slash}TOSC2))") (class "Default")
      (node (ref "C2") (pin "2") (pinfunction "2_2") (pintype "passive"))
      (node (ref "U1") (pin "10") (pinfunction "PB7(XTAL2/TOSC2)_10") (pintype "bidirectional"))
      (node (ref "XTAL") (pin "1") (pinfunction "1_1") (pintype "passive"))
    )
    (net (code "52") (name "Net-(U1-PD5(T1))") (class "Default")
      (node (ref "J1") (pin "1") (pinfunction "1_1") (pintype "passive"))
      (node (ref "U1") (pin "11") (pinfunction "PD5(T1)_11") (pintype "bidirectional"))
    )
    (net (code "53") (name "Net-(U1-PD6(AIN0))") (class "Default")
      (node (ref "J1") (pin "2") (pinfunction "2_2") (pintype "passive"))
      (node (ref "U1") (pin "12") (pinfunction "PD6(AIN0)_12") (pintype "bidirectional"))
    )
    (net (code "54") (name "Net-(U1-PD7(AIN1))") (class "Default")
      (node (ref "J1") (pin "3") (pinfunction "3_3") (pintype "passive"))
      (node (ref "U1") (pin "13") (pinfunction "PD7(AIN1)_13") (pintype "bidirectional"))
    )
    (net (code "55") (name "Net-(U2-AC1)") (class "Default")
      (node (ref "R20") (pin "2") (pinfunction "2_2") (pintype "passive"))
      (node (ref "U2") (pin "1") (pinfunction "AC1_1") (pintype "passive"))
    )
    (net (code "56") (name "Net-(VR1-CW)") (class "Default")
      (node (ref "R17") (pin "2") (pinfunction "2_2") (pintype "passive"))
      (node (ref "VR1") (pin "2") (pinfunction "WIPER_2") (pintype "passive"))
      (node (ref "VR1") (pin "3") (pinfunction "CW_3") (pintype "passive"))
    )
    (net (code "57") (name "Net-(XFMR1-3)") (class "Default")
      (node (ref "D4") (pin "A") (pinfunction "A_A") (pintype "passive"))
      (node (ref "D5") (pin "A") (pinfunction "A_A") (pintype "passive"))
      (node (ref "XFMR1") (pin "6") (pinfunction "5_6") (pintype "passive"))
      (node (ref "XFMR1") (pin "8") (pinfunction "3_8") (pintype "passive"))
    )
    (net (code "58") (name "Net-(XFMR1-4)") (class "Default")
      (node (ref "F1") (pin "1") (pinfunction "1_1") (pintype "passive"))
      (node (ref "XFMR1") (pin "5") (pinfunction "6_5") (pintype "passive"))
      (node (ref "XFMR1") (pin "7") (pinfunction "4_7") (pintype "passive"))
    )
    (net (code "59") (name "unconnected-(IC1D-OUT-Pad14)") (class "Default")
      (node (ref "IC1") (pin "14") (pinfunction "OUT_14") (pintype "output"))
    )
    (net (code "60") (name "unconnected-(J1-Pad8)") (class "Default")
      (node (ref "J1") (pin "8") (pinfunction "8_8") (pintype "passive"))
    )
    (net (code "61") (name "unconnected-(J12-Pad1)") (class "Default")
      (node (ref "J12") (pin "1") (pinfunction "1_1") (pintype "passive"))
    )
    (net (code "62") (name "unconnected-(J12-Pad2)") (class "Default")
      (node (ref "J12") (pin "2") (pinfunction "2_2") (pintype "passive"))
    )
    (net (code "63") (name "unconnected-(LS1-Pad+)") (class "Default")
      (node (ref "LS1") (pin "+") (pinfunction "+_+") (pintype "bidirectional"))
    )
    (net (code "64") (name "unconnected-(LS1-Pad-)") (class "Default")
      (node (ref "LS1") (pin "-") (pinfunction "-_-") (pintype "bidirectional"))
    )
    (net (code "65") (name "unconnected-(RTD-1-PadP$1)") (class "Default")
      (node (ref "RTD") (pin "P$1") (pinfunction "1_P$1") (pintype "passive"))
    )
    (net (code "66") (name "unconnected-(RTD-2-PadP$2)") (class "Default")
      (node (ref "RTD") (pin "P$2") (pinfunction "2_P$2") (pintype "passive"))
    )
    (net (code "67") (name "unconnected-(U1-PC1(ADC1)-Pad24)") (class "Default")
      (node (ref "U1") (pin "24") (pinfunction "PC1(ADC1)_24") (pintype "bidirectional"))
    )
    (net (code "68") (name "unconnected-(U1-PC2(ADC2)-Pad25)") (class "Default")
      (node (ref "U1") (pin "25") (pinfunction "PC2(ADC2)_25") (pintype "bidirectional"))
    )
    (net (code "69") (name "unconnected-(U1-PC3(ADC3)-Pad26)") (class "Default")
      (node (ref "U1") (pin "26") (pinfunction "PC3(ADC3)_26") (pintype "bidirectional"))
    )
  )
)
